# SCB_Top_Sheet.net
KiCad netlist of a schematic drawn in Altium Designer
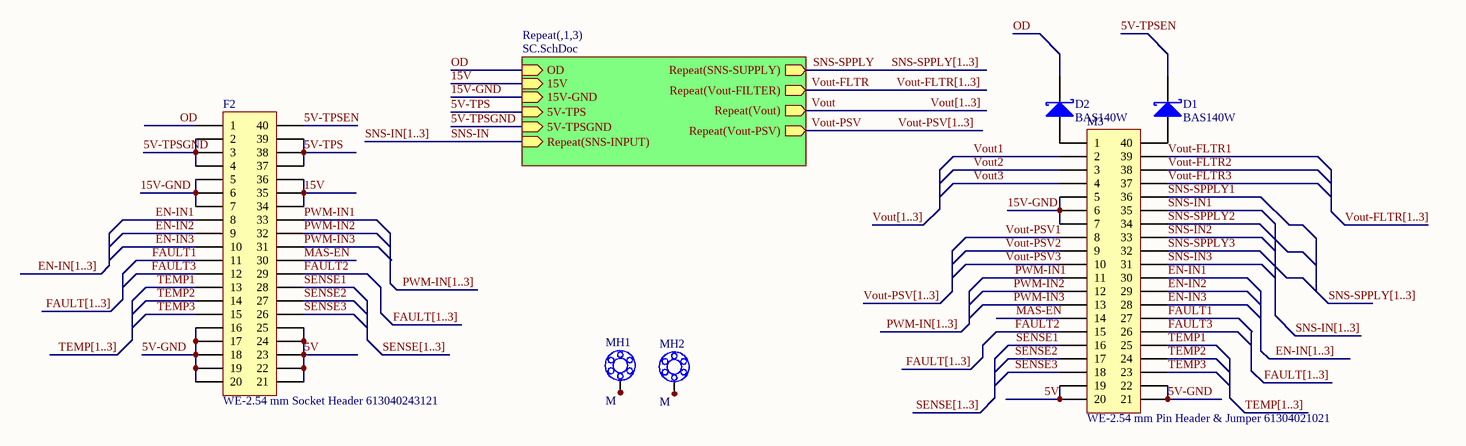
[diagram p0: SCB_Top_Sheet.SchDoc]

(export (version "E")
  (design (tool "Eeschema 10.0.6"))
  (components
    (comp (ref "D1")
      (value "BAS140W")
      (footprint "SOD-323")
      (description "Silicon AF Schottky Diode for High-Speed Switching")
      (fields (field (name "PUBLISHER") "Altium Limited"))
      (libsource (lib "Infineon Discrete Diode") (part "BAS140W"))
    )
    (comp (ref "D2")
      (value "BAS140W")
      (footprint "SOD-323")
      (description "Silicon AF Schottky Diode for High-Speed Switching")
      (fields (field (name "PUBLISHER") "Altium Limited"))
      (libsource (lib "Infineon Discrete Diode") (part "BAS140W"))
    )
    (comp (ref "F2")
      (value "WE-2.54 mm Socket Header 613040243121")
      (footprint "613040243121")
      (description "WR-PHD 2.54 mm Angled Socket Header")
      (fields
        (field (name "MANUFACTURER") "Würth Elektronik eiSos GmbH")
        (field (name "PARTNO") "613040243121")
        (field (name "CREATED BY") "Karrer Zheng")
      )
      (libsource (lib "WE_WR-PHD_Socket Header_2.54mm_rev15c") (part "WE-2.54 mm Socket Header 613040243121"))
    )
    (comp (ref "M3")
      (value "WE-2.54 mm Pin Header & Jumper 61304021021")
      (footprint "61304021021")
      (description "WR-PHD 2.54 mm Angled Dual Pin Header")
      (fields
        (field (name "MANUFACTURER") "Würth Elektronik eiSos GmbH")
        (field (name "PARTNO") "61304021021")
        (field (name "CREATED BY") "Karrer Zheng")
      )
      (libsource (lib "WE_WR-PHD_Pin Header_2.54mm_rev15c") (part "WE-2.54 mm Pin Header & Jumper 61304021021"))
    )
    (comp (ref "MH1")
      (value "M")
      (footprint "MOUNTING")
      (description "MOUNTING HOLE - NON INSTALLABLE")
      (libsource (lib "vh_altium_library") (part "MOUNTING"))
    )
    (comp (ref "MH2")
      (value "M")
      (footprint "MOUNTING")
      (description "MOUNTING HOLE - NON INSTALLABLE")
      (libsource (lib "vh_altium_library") (part "MOUNTING"))
    )
  )
  (nets
    (net (code "1") (name "/5V") (class "Default")
      (node (ref "F2") (pin "21") (pinfunction "21_21") (pintype "passive"))
      (node (ref "F2") (pin "22") (pinfunction "22_22") (pintype "passive"))
      (node (ref "F2") (pin "23") (pinfunction "23_23") (pintype "passive"))
      (node (ref "F2") (pin "24") (pinfunction "24_24") (pintype "passive"))
      (node (ref "F2") (pin "25") (pinfunction "25_25") (pintype "passive"))
      (node (ref "M3") (pin "19") (pinfunction "19_19") (pintype "passive"))
      (node (ref "M3") (pin "20") (pinfunction "20_20") (pintype "passive"))
    )
    (net (code "2") (name "/5V-GND") (class "Default")
      (node (ref "F2") (pin "16") (pinfunction "16_16") (pintype "passive"))
      (node (ref "F2") (pin "17") (pinfunction "17_17") (pintype "passive"))
      (node (ref "F2") (pin "18") (pinfunction "18_18") (pintype "passive"))
      (node (ref "F2") (pin "19") (pinfunction "19_19") (pintype "passive"))
      (node (ref "F2") (pin "20") (pinfunction "20_20") (pintype "passive"))
      (node (ref "M3") (pin "21") (pinfunction "21_21") (pintype "passive"))
      (node (ref "M3") (pin "22") (pinfunction "22_22") (pintype "passive"))
    )
    (net (code "3") (name "/5V-TPS") (class "Default")
      (node (ref "F2") (pin "37") (pinfunction "37_37") (pintype "passive"))
      (node (ref "F2") (pin "38") (pinfunction "38_38") (pintype "passive"))
      (node (ref "F2") (pin "39") (pinfunction "39_39") (pintype "passive"))
    )
    (net (code "4") (name "/5V-TPSEN") (class "Default")
      (node (ref "D1") (pin "1") (pinfunction "K_1") (pintype "passive"))
      (node (ref "F2") (pin "40") (pinfunction "40_40") (pintype "passive"))
    )
    (net (code "5") (name "/5V-TPSGND") (class "Default")
      (node (ref "F2") (pin "2") (pinfunction "2_2") (pintype "passive"))
      (node (ref "F2") (pin "3") (pinfunction "3_3") (pintype "passive"))
      (node (ref "F2") (pin "4") (pinfunction "4_4") (pintype "passive"))
    )
    (net (code "6") (name "/15V") (class "Default")
      (node (ref "F2") (pin "34") (pinfunction "34_34") (pintype "passive"))
      (node (ref "F2") (pin "35") (pinfunction "35_35") (pintype "passive"))
      (node (ref "F2") (pin "36") (pinfunction "36_36") (pintype "passive"))
    )
    (net (code "7") (name "/15V-GND") (class "Default")
      (node (ref "F2") (pin "5") (pinfunction "5_5") (pintype "passive"))
      (node (ref "F2") (pin "6") (pinfunction "6_6") (pintype "passive"))
      (node (ref "F2") (pin "7") (pinfunction "7_7") (pintype "passive"))
      (node (ref "M3") (pin "5") (pinfunction "5_5") (pintype "passive"))
      (node (ref "M3") (pin "6") (pinfunction "6_6") (pintype "passive"))
      (node (ref "M3") (pin "7") (pinfunction "7_7") (pintype "passive"))
    )
    (net (code "8") (name "/EN-IN1") (class "Default")
      (node (ref "F2") (pin "8") (pinfunction "8_8") (pintype "passive"))
      (node (ref "M3") (pin "30") (pinfunction "30_30") (pintype "passive"))
    )
    (net (code "9") (name "/EN-IN2") (class "Default")
      (node (ref "F2") (pin "9") (pinfunction "9_9") (pintype "passive"))
      (node (ref "M3") (pin "29") (pinfunction "29_29") (pintype "passive"))
    )
    (net (code "10") (name "/EN-IN3") (class "Default")
      (node (ref "F2") (pin "10") (pinfunction "10_10") (pintype "passive"))
      (node (ref "M3") (pin "28") (pinfunction "28_28") (pintype "passive"))
    )
    (net (code "12") (name "/FAULT1") (class "Default")
      (node (ref "F2") (pin "11") (pinfunction "11_11") (pintype "passive"))
      (node (ref "M3") (pin "27") (pinfunction "27_27") (pintype "passive"))
    )
    (net (code "13") (name "/FAULT2") (class "Default")
      (node (ref "F2") (pin "29") (pinfunction "29_29") (pintype "passive"))
      (node (ref "M3") (pin "15") (pinfunction "15_15") (pintype "passive"))
    )
    (net (code "14") (name "/FAULT3") (class "Default")
      (node (ref "F2") (pin "12") (pinfunction "12_12") (pintype "passive"))
      (node (ref "M3") (pin "26") (pinfunction "26_26") (pintype "passive"))
    )
    (net (code "16") (name "/MAS-EN") (class "Default")
      (node (ref "F2") (pin "30") (pinfunction "30_30") (pintype "passive"))
      (node (ref "M3") (pin "14") (pinfunction "14_14") (pintype "passive"))
    )
    (net (code "17") (name "/OD") (class "Default")
      (node (ref "D2") (pin "1") (pinfunction "K_1") (pintype "passive"))
      (node (ref "F2") (pin "1") (pinfunction "1_1") (pintype "passive"))
    )
    (net (code "18") (name "/PWM-IN1") (class "Default")
      (node (ref "F2") (pin "33") (pinfunction "33_33") (pintype "passive"))
      (node (ref "M3") (pin "11") (pinfunction "11_11") (pintype "passive"))
    )
    (net (code "19") (name "/PWM-IN2") (class "Default")
      (node (ref "F2") (pin "32") (pinfunction "32_32") (pintype "passive"))
      (node (ref "M3") (pin "12") (pinfunction "12_12") (pintype "passive"))
    )
    (net (code "20") (name "/PWM-IN3") (class "Default")
      (node (ref "F2") (pin "31") (pinfunction "31_31") (pintype "passive"))
      (node (ref "M3") (pin "13") (pinfunction "13_13") (pintype "passive"))
    )
    (net (code "22") (name "/SENSE1") (class "Default")
      (node (ref "F2") (pin "28") (pinfunction "28_28") (pintype "passive"))
      (node (ref "M3") (pin "16") (pinfunction "16_16") (pintype "passive"))
    )
    (net (code "23") (name "/SENSE2") (class "Default")
      (node (ref "F2") (pin "27") (pinfunction "27_27") (pintype "passive"))
      (node (ref "M3") (pin "17") (pinfunction "17_17") (pintype "passive"))
    )
    (net (code "24") (name "/SENSE3") (class "Default")
      (node (ref "F2") (pin "26") (pinfunction "26_26") (pintype "passive"))
      (node (ref "M3") (pin "18") (pinfunction "18_18") (pintype "passive"))
    )
    (net (code "27") (name "/SNS-IN1") (class "Default")
      (node (ref "M3") (pin "35") (pinfunction "35_35") (pintype "passive"))
    )
    (net (code "28") (name "/SNS-IN2") (class "Default")
      (node (ref "M3") (pin "33") (pinfunction "33_33") (pintype "passive"))
    )
    (net (code "29") (name "/SNS-IN3") (class "Default")
      (node (ref "M3") (pin "31") (pinfunction "31_31") (pintype "passive"))
    )
    (net (code "32") (name "/SNS-SPPLY1") (class "Default")
      (node (ref "M3") (pin "36") (pinfunction "36_36") (pintype "passive"))
    )
    (net (code "33") (name "/SNS-SPPLY2") (class "Default")
      (node (ref "M3") (pin "34") (pinfunction "34_34") (pintype "passive"))
    )
    (net (code "34") (name "/SNS-SPPLY3") (class "Default")
      (node (ref "M3") (pin "32") (pinfunction "32_32") (pintype "passive"))
    )
    (net (code "36") (name "/TEMP1") (class "Default")
      (node (ref "F2") (pin "13") (pinfunction "13_13") (pintype "passive"))
      (node (ref "M3") (pin "25") (pinfunction "25_25") (pintype "passive"))
    )
    (net (code "37") (name "/TEMP2") (class "Default")
      (node (ref "F2") (pin "14") (pinfunction "14_14") (pintype "passive"))
      (node (ref "M3") (pin "24") (pinfunction "24_24") (pintype "passive"))
    )
    (net (code "38") (name "/TEMP3") (class "Default")
      (node (ref "F2") (pin "15") (pinfunction "15_15") (pintype "passive"))
      (node (ref "M3") (pin "23") (pinfunction "23_23") (pintype "passive"))
    )
    (net (code "42") (name "/Vout-FLTR1") (class "Default")
      (node (ref "M3") (pin "39") (pinfunction "39_39") (pintype "passive"))
    )
    (net (code "43") (name "/Vout-FLTR2") (class "Default")
      (node (ref "M3") (pin "38") (pinfunction "38_38") (pintype "passive"))
    )
    (net (code "44") (name "/Vout-FLTR3") (class "Default")
      (node (ref "M3") (pin "37") (pinfunction "37_37") (pintype "passive"))
    )
    (net (code "47") (name "/Vout-PSV1") (class "Default")
      (node (ref "M3") (pin "8") (pinfunction "8_8") (pintype "passive"))
    )
    (net (code "48") (name "/Vout-PSV2") (class "Default")
      (node (ref "M3") (pin "9") (pinfunction "9_9") (pintype "passive"))
    )
    (net (code "49") (name "/Vout-PSV3") (class "Default")
      (node (ref "M3") (pin "10") (pinfunction "10_10") (pintype "passive"))
    )
    (net (code "51") (name "/Vout1") (class "Default")
      (node (ref "M3") (pin "2") (pinfunction "2_2") (pintype "passive"))
    )
    (net (code "52") (name "/Vout2") (class "Default")
      (node (ref "M3") (pin "3") (pinfunction "3_3") (pintype "passive"))
    )
    (net (code "53") (name "/Vout3") (class "Default")
      (node (ref "M3") (pin "4") (pinfunction "4_4") (pintype "passive"))
    )
    (net (code "55") (name "Net-(D1-A)") (class "Default")
      (node (ref "D1") (pin "2") (pinfunction "A_2") (pintype "passive"))
      (node (ref "M3") (pin "40") (pinfunction "40_40") (pintype "passive"))
    )
    (net (code "56") (name "Net-(D2-A)") (class "Default")
      (node (ref "D2") (pin "2") (pinfunction "A_2") (pintype "passive"))
      (node (ref "M3") (pin "1") (pinfunction "1_1") (pintype "passive"))
    )
    (net (code "57") (name "Net-(MH1-Pad1)") (class "Default")
      (node (ref "MH1") (pin "1") (pinfunction "1_1") (pintype "passive"))
      (node (ref "MH1") (pin "2") (pinfunction "2_2") (pintype "passive"))
      (node (ref "MH1") (pin "3") (pinfunction "3_3") (pintype "passive"))
      (node (ref "MH1") (pin "4") (pinfunction "4_4") (pintype "passive"))
      (node (ref "MH1") (pin "5") (pinfunction "5_5") (pintype "passive"))
      (node (ref "MH1") (pin "6") (pinfunction "6_6") (pintype "passive"))
      (node (ref "MH1") (pin "7") (pinfunction "7_7") (pintype "passive"))
      (node (ref "MH1") (pin "8") (pinfunction "8_8") (pintype "passive"))
      (node (ref "MH1") (pin "9") (pinfunction "9_9") (pintype "passive"))
    )
    (net (code "58") (name "Net-(MH2-Pad1)") (class "Default")
      (node (ref "MH2") (pin "1") (pinfunction "1_1") (pintype "passive"))
      (node (ref "MH2") (pin "2") (pinfunction "2_2") (pintype "passive"))
      (node (ref "MH2") (pin "3") (pinfunction "3_3") (pintype "passive"))
      (node (ref "MH2") (pin "4") (pinfunction "4_4") (pintype "passive"))
      (node (ref "MH2") (pin "5") (pinfunction "5_5") (pintype "passive"))
      (node (ref "MH2") (pin "6") (pinfunction "6_6") (pintype "passive"))
      (node (ref "MH2") (pin "7") (pinfunction "7_7") (pintype "passive"))
      (node (ref "MH2") (pin "8") (pinfunction "8_8") (pintype "passive"))
      (node (ref "MH2") (pin "9") (pinfunction "9_9") (pintype "passive"))
    )
  )
)
